# kibannISE2024_control.net
KiCad netlist of a schematic drawn in EAGLE
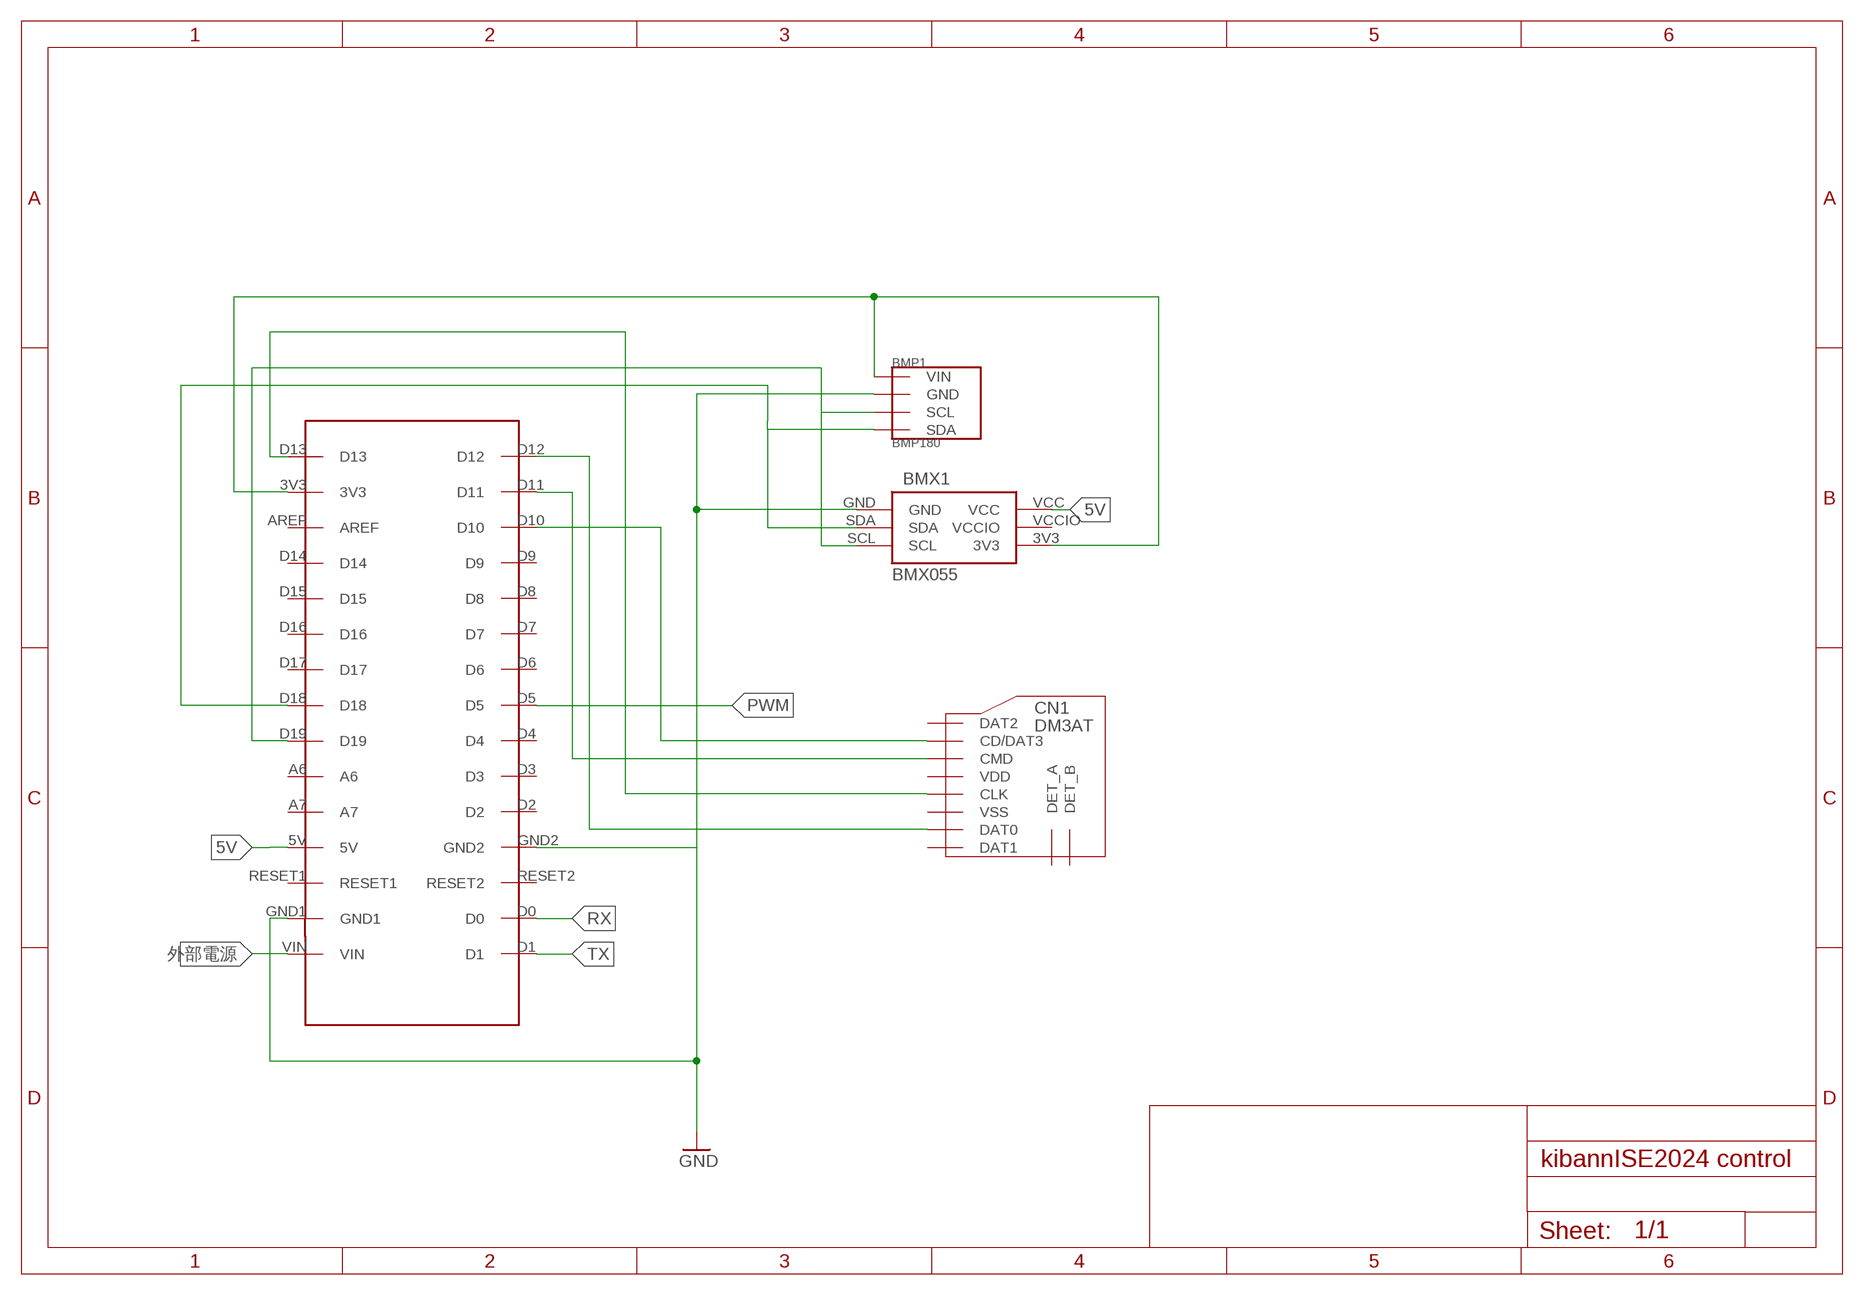
[diagram p0: schematic, sheet 1]

(export (version "E")
  (design (tool "Eeschema 10.0.6"))
  (components
    (comp (ref "BMP1")
      (value "BMP180")
      (footprint "eagle-import:GY-68")
      (libsource (lib "eagle-import") (part "BMP180"))
    )
    (comp (ref "BMX1")
      (value "BMX055")
      (footprint "eagle-import:BMX055")
      (libsource (lib "eagle-import") (part "BMX055"))
    )
    (comp (ref "CN1")
      (value "DM3AT")
      (footprint "eagle-import:DM3AT")
      (libsource (lib "eagle-import") (part "DM3AT"))
    )
    (comp (ref "U$1")
      (value "ARDUINONANO")
      (footprint "eagle-import:ARDUINONANO")
      (libsource (lib "eagle-import") (part "ARDUINONANO"))
    )
  )
  (nets
    (net (code "1") (name "/VCCIO") (class "Default")
      (node (ref "BMX1") (pin "VCCIO") (pinfunction "VCCIO_VCCIO") (pintype "power_in"))
    )
    (net (code "2") (name "5V") (class "Default")
      (node (ref "BMX1") (pin "VCC") (pinfunction "VCC_VCC") (pintype "power_in"))
      (node (ref "U$1") (pin "5V") (pinfunction "5V_5V") (pintype "bidirectional"))
    )
    (net (code "3") (name "GND") (class "Default")
      (node (ref "BMP1") (pin "P2") (pinfunction "GND_P2") (pintype "bidirectional"))
      (node (ref "BMX1") (pin "GND") (pinfunction "GND_GND") (pintype "power_in"))
      (node (ref "U$1") (pin "GND1") (pinfunction "GND1_GND1") (pintype "bidirectional"))
      (node (ref "U$1") (pin "GND2") (pinfunction "GND2_GND2") (pintype "bidirectional"))
    )
    (net (code "4") (name "Net-(BMP1-SCL)") (class "Default")
      (node (ref "BMP1") (pin "P3") (pinfunction "SCL_P3") (pintype "bidirectional"))
      (node (ref "BMX1") (pin "SCL") (pinfunction "SCL_SCL") (pintype "bidirectional"))
      (node (ref "U$1") (pin "D19") (pinfunction "D19_D19") (pintype "bidirectional"))
    )
    (net (code "5") (name "Net-(BMP1-SDA)") (class "Default")
      (node (ref "BMP1") (pin "P4") (pinfunction "SDA_P4") (pintype "bidirectional"))
      (node (ref "BMX1") (pin "SDA") (pinfunction "SDA_SDA") (pintype "bidirectional"))
      (node (ref "U$1") (pin "D18") (pinfunction "D18_D18") (pintype "bidirectional"))
    )
    (net (code "6") (name "Net-(BMP1-VIN)") (class "Default")
      (node (ref "BMP1") (pin "P1") (pinfunction "VIN_P1") (pintype "bidirectional"))
      (node (ref "BMX1") (pin "3V3") (pinfunction "3V3_3V3") (pintype "power_in"))
      (node (ref "U$1") (pin "3V3") (pinfunction "3V3_3V3") (pintype "bidirectional"))
    )
    (net (code "7") (name "Net-(CN1-PadCD{slash}DAT3)") (class "Default")
      (node (ref "CN1") (pin "CD/DAT3") (pinfunction "CD/DAT3_CD/DAT3") (pintype "bidirectional"))
      (node (ref "U$1") (pin "D10") (pinfunction "D10_D10") (pintype "bidirectional"))
    )
    (net (code "8") (name "Net-(CN1-PadCLK)") (class "Default")
      (node (ref "CN1") (pin "CLK") (pinfunction "CLK_CLK") (pintype "bidirectional"))
      (node (ref "U$1") (pin "D13") (pinfunction "D13_D13") (pintype "bidirectional"))
    )
    (net (code "9") (name "Net-(CN1-PadCMD)") (class "Default")
      (node (ref "CN1") (pin "CMD") (pinfunction "CMD_CMD") (pintype "bidirectional"))
      (node (ref "U$1") (pin "D11") (pinfunction "D11_D11") (pintype "bidirectional"))
    )
    (net (code "10") (name "Net-(CN1-PadDAT0)") (class "Default")
      (node (ref "CN1") (pin "DAT0") (pinfunction "DAT0_DAT0") (pintype "bidirectional"))
      (node (ref "U$1") (pin "D12") (pinfunction "D12_D12") (pintype "bidirectional"))
    )
    (net (code "11") (name "PWM") (class "Default")
      (node (ref "U$1") (pin "D5") (pinfunction "D5_D5") (pintype "bidirectional"))
    )
    (net (code "12") (name "RX") (class "Default")
      (node (ref "U$1") (pin "D0") (pinfunction "D0_D0") (pintype "bidirectional"))
    )
    (net (code "13") (name "TX") (class "Default")
      (node (ref "U$1") (pin "D1") (pinfunction "D1_D1") (pintype "bidirectional"))
    )
    (net (code "14") (name "unconnected-(CN1-PadDAT1)") (class "Default")
      (node (ref "CN1") (pin "DAT1") (pinfunction "DAT1_DAT1") (pintype "bidirectional"))
    )
    (net (code "15") (name "unconnected-(CN1-PadDAT2)") (class "Default")
      (node (ref "CN1") (pin "DAT2") (pinfunction "DAT2_DAT2") (pintype "bidirectional"))
    )
    (net (code "16") (name "unconnected-(CN1-PadDET_A)") (class "Default")
      (node (ref "CN1") (pin "DET_A") (pinfunction "DET_A_DET_A") (pintype "bidirectional"))
    )
    (net (code "17") (name "unconnected-(CN1-PadDET_B)") (class "Default")
      (node (ref "CN1") (pin "DET_B") (pinfunction "DET_B_DET_B") (pintype "bidirectional"))
    )
    (net (code "18") (name "unconnected-(CN1-PadVDD)") (class "Default")
      (node (ref "CN1") (pin "VDD") (pinfunction "VDD_VDD") (pintype "bidirectional"))
    )
    (net (code "19") (name "unconnected-(CN1-PadVSS)") (class "Default")
      (node (ref "CN1") (pin "VSS") (pinfunction "VSS_VSS") (pintype "bidirectional"))
    )
    (net (code "20") (name "unconnected-(U$1-PadA6)") (class "Default")
      (node (ref "U$1") (pin "A6") (pinfunction "A6_A6") (pintype "bidirectional"))
    )
    (net (code "21") (name "unconnected-(U$1-PadA7)") (class "Default")
      (node (ref "U$1") (pin "A7") (pinfunction "A7_A7") (pintype "bidirectional"))
    )
    (net (code "22") (name "unconnected-(U$1-PadAREF)") (class "Default")
      (node (ref "U$1") (pin "AREF") (pinfunction "AREF_AREF") (pintype "bidirectional"))
    )
    (net (code "23") (name "unconnected-(U$1-PadD2)") (class "Default")
      (node (ref "U$1") (pin "D2") (pinfunction "D2_D2") (pintype "bidirectional"))
    )
    (net (code "24") (name "unconnected-(U$1-PadD3)") (class "Default")
      (node (ref "U$1") (pin "D3") (pinfunction "D3_D3") (pintype "bidirectional"))
    )
    (net (code "25") (name "unconnected-(U$1-PadD4)") (class "Default")
      (node (ref "U$1") (pin "D4") (pinfunction "D4_D4") (pintype "bidirectional"))
    )
    (net (code "26") (name "unconnected-(U$1-PadD6)") (class "Default")
      (node (ref "U$1") (pin "D6") (pinfunction "D6_D6") (pintype "bidirectional"))
    )
    (net (code "27") (name "unconnected-(U$1-PadD7)") (class "Default")
      (node (ref "U$1") (pin "D7") (pinfunction "D7_D7") (pintype "bidirectional"))
    )
    (net (code "28") (name "unconnected-(U$1-PadD8)") (class "Default")
      (node (ref "U$1") (pin "D8") (pinfunction "D8_D8") (pintype "bidirectional"))
    )
    (net (code "29") (name "unconnected-(U$1-PadD9)") (class "Default")
      (node (ref "U$1") (pin "D9") (pinfunction "D9_D9") (pintype "bidirectional"))
    )
    (net (code "30") (name "unconnected-(U$1-PadD14)") (class "Default")
      (node (ref "U$1") (pin "D14") (pinfunction "D14_D14") (pintype "bidirectional"))
    )
    (net (code "31") (name "unconnected-(U$1-PadD15)") (class "Default")
      (node (ref "U$1") (pin "D15") (pinfunction "D15_D15") (pintype "bidirectional"))
    )
    (net (code "32") (name "unconnected-(U$1-PadD16)") (class "Default")
      (node (ref "U$1") (pin "D16") (pinfunction "D16_D16") (pintype "bidirectional"))
    )
    (net (code "33") (name "unconnected-(U$1-PadD17)") (class "Default")
      (node (ref "U$1") (pin "D17") (pinfunction "D17_D17") (pintype "bidirectional"))
    )
    (net (code "34") (name "unconnected-(U$1-PadRESET1)") (class "Default")
      (node (ref "U$1") (pin "RESET1") (pinfunction "RESET1_RESET1") (pintype "bidirectional"))
    )
    (net (code "35") (name "unconnected-(U$1-PadRESET2)") (class "Default")
      (node (ref "U$1") (pin "RESET2") (pinfunction "RESET2_RESET2") (pintype "bidirectional"))
    )
    (net (code "36") (name "外部電源") (class "Default")
      (node (ref "U$1") (pin "VIN") (pinfunction "VIN_VIN") (pintype "bidirectional"))
    )
  )
)
